# PANDASchematic.net
KiCad netlist of a schematic drawn in EAGLE
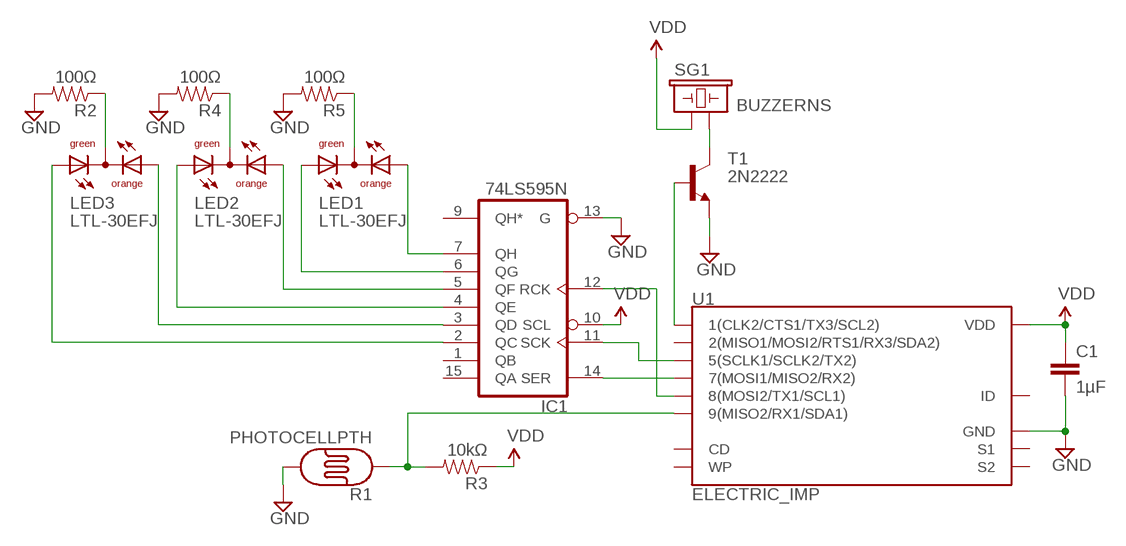
[diagram p0: schematic, sheet 1]

(export (version "E")
  (design (tool "Eeschema 10.0.6"))
  (components
    (comp (ref "C1")
      (value "1µF")
      (footprint "eagle-import:CAP-PTH-SMALL")
      (libsource (lib "eagle-import") (part "CAPPTH"))
    )
    (comp (ref "IC1")
      (value "74LS595N")
      (footprint "eagle-import:DIL16")
      (libsource (lib "eagle-import") (part "74595NLS"))
    )
    (comp (ref "LED1")
      (value "LTL-30EFJ")
      (footprint "eagle-import:TLUV5300")
      (libsource (lib "eagle-import") (part "TLUV5300"))
    )
    (comp (ref "LED2")
      (value "LTL-30EFJ")
      (footprint "eagle-import:TLUV5300")
      (libsource (lib "eagle-import") (part "TLUV5300"))
    )
    (comp (ref "LED3")
      (value "LTL-30EFJ")
      (footprint "eagle-import:TLUV5300")
      (libsource (lib "eagle-import") (part "TLUV5300"))
    )
    (comp (ref "R1")
      (value "PHOTOCELLPTH")
      (footprint "eagle-import:PHOTOCELL")
      (libsource (lib "eagle-import") (part "PHOTOCELLPTH"))
    )
    (comp (ref "R2")
      (value "100Ω")
      (footprint "eagle-import:AXIAL-0.3")
      (libsource (lib "eagle-import") (part "RESISTORAXIAL-0.3"))
    )
    (comp (ref "R3")
      (value "10kΩ")
      (footprint "eagle-import:AXIAL-0.3")
      (libsource (lib "eagle-import") (part "RESISTORAXIAL-0.3"))
    )
    (comp (ref "R4")
      (value "100Ω")
      (footprint "eagle-import:AXIAL-0.3")
      (libsource (lib "eagle-import") (part "RESISTORAXIAL-0.3"))
    )
    (comp (ref "R5")
      (value "100Ω")
      (footprint "eagle-import:AXIAL-0.3")
      (libsource (lib "eagle-import") (part "RESISTORAXIAL-0.3"))
    )
    (comp (ref "SG1")
      (value "BUZZERNS")
      (footprint "eagle-import:BUZZER-12MM-NS")
      (libsource (lib "eagle-import") (part "BUZZERNS"))
    )
    (comp (ref "T1")
      (value "2N2222")
      (footprint "eagle-import:TO92-EBC-OVAL")
      (libsource (lib "eagle-import") (part "2N2222"))
    )
    (comp (ref "U1")
      (value "ELECTRIC_IMP")
      (footprint "eagle-import:SD_1_1")
      (libsource (lib "eagle-import") (part "ELECTRIC_IMP"))
    )
  )
  (nets
    (net (code "1") (name "GND") (class "Default")
      (node (ref "C1") (pin "2") (pinfunction "2_2") (pintype "passive"))
      (node (ref "IC1") (pin "13") (pinfunction "G_13") (pintype "input"))
      (node (ref "R1") (pin "2") (pinfunction "P$2_2") (pintype "bidirectional"))
      (node (ref "R2") (pin "P$2") (pinfunction "2_P$2") (pintype "passive"))
      (node (ref "R4") (pin "P$2") (pinfunction "2_P$2") (pintype "passive"))
      (node (ref "R5") (pin "P$2") (pinfunction "2_P$2") (pintype "passive"))
      (node (ref "T1") (pin "E") (pinfunction "E_E") (pintype "passive"))
      (node (ref "U1") (pin "3") (pinfunction "GND_3") (pintype "bidirectional"))
    )
    (net (code "2") (name "Net-(IC1A-QC)") (class "Default")
      (node (ref "IC1") (pin "2") (pinfunction "QC_2") (pintype "tri_state"))
      (node (ref "LED3") (pin "AG") (pinfunction "AG_AG") (pintype "passive"))
    )
    (net (code "3") (name "Net-(IC1A-QD)") (class "Default")
      (node (ref "IC1") (pin "3") (pinfunction "QD_3") (pintype "tri_state"))
      (node (ref "LED3") (pin "AO") (pinfunction "AO_AO") (pintype "passive"))
    )
    (net (code "4") (name "Net-(IC1A-QE)") (class "Default")
      (node (ref "IC1") (pin "4") (pinfunction "QE_4") (pintype "tri_state"))
      (node (ref "LED2") (pin "AG") (pinfunction "AG_AG") (pintype "passive"))
    )
    (net (code "5") (name "Net-(IC1A-QF)") (class "Default")
      (node (ref "IC1") (pin "5") (pinfunction "QF_5") (pintype "tri_state"))
      (node (ref "LED2") (pin "AO") (pinfunction "AO_AO") (pintype "passive"))
    )
    (net (code "6") (name "Net-(IC1A-QG)") (class "Default")
      (node (ref "IC1") (pin "6") (pinfunction "QG_6") (pintype "tri_state"))
      (node (ref "LED1") (pin "AG") (pinfunction "AG_AG") (pintype "passive"))
    )
    (net (code "7") (name "Net-(IC1A-QH)") (class "Default")
      (node (ref "IC1") (pin "7") (pinfunction "QH_7") (pintype "tri_state"))
      (node (ref "LED1") (pin "AO") (pinfunction "AO_AO") (pintype "passive"))
    )
    (net (code "8") (name "Net-(IC1A-RCK)") (class "Default")
      (node (ref "IC1") (pin "12") (pinfunction "RCK_12") (pintype "input"))
      (node (ref "U1") (pin "8") (pinfunction "8(MOSI2/TX1/SCL1)_8") (pintype "bidirectional"))
    )
    (net (code "9") (name "Net-(IC1A-SCK)") (class "Default")
      (node (ref "IC1") (pin "11") (pinfunction "SCK_11") (pintype "input"))
      (node (ref "U1") (pin "5") (pinfunction "5(SCLK1/SCLK2/TX2)_5") (pintype "bidirectional"))
    )
    (net (code "10") (name "Net-(IC1A-SER)") (class "Default")
      (node (ref "IC1") (pin "14") (pinfunction "SER_14") (pintype "input"))
      (node (ref "U1") (pin "7") (pinfunction "7(MOSI1/MISO2/RX2)_7") (pintype "bidirectional"))
    )
    (net (code "11") (name "Net-(R1-P$1)") (class "Default")
      (node (ref "R1") (pin "1") (pinfunction "P$1_1") (pintype "bidirectional"))
      (node (ref "R3") (pin "P$2") (pinfunction "2_P$2") (pintype "passive"))
      (node (ref "U1") (pin "9") (pinfunction "9(MISO2/RX1/SDA1)_9") (pintype "bidirectional"))
    )
    (net (code "12") (name "Net-(R2-1)") (class "Default")
      (node (ref "LED3") (pin "CC") (pinfunction "CC_CC") (pintype "passive"))
      (node (ref "R2") (pin "P$1") (pinfunction "1_P$1") (pintype "passive"))
    )
    (net (code "13") (name "Net-(R4-1)") (class "Default")
      (node (ref "LED2") (pin "CC") (pinfunction "CC_CC") (pintype "passive"))
      (node (ref "R4") (pin "P$1") (pinfunction "1_P$1") (pintype "passive"))
    )
    (net (code "14") (name "Net-(R5-1)") (class "Default")
      (node (ref "LED1") (pin "CC") (pinfunction "CC_CC") (pintype "passive"))
      (node (ref "R5") (pin "P$1") (pinfunction "1_P$1") (pintype "passive"))
    )
    (net (code "15") (name "Net-(SG1-2)") (class "Default")
      (node (ref "SG1") (pin "-") (pinfunction "2_-") (pintype "passive"))
      (node (ref "T1") (pin "C") (pinfunction "C_C") (pintype "passive"))
    )
    (net (code "16") (name "Net-(U1-1(CLK2{slash}CTS1{slash}TX3{slash}SCL2))") (class "Default")
      (node (ref "T1") (pin "B") (pinfunction "B_B") (pintype "passive"))
      (node (ref "U1") (pin "1") (pinfunction "1(CLK2/CTS1/TX3/SCL2)_1") (pintype "bidirectional"))
    )
    (net (code "17") (name "VDD") (class "Default")
      (node (ref "C1") (pin "1") (pinfunction "1_1") (pintype "passive"))
      (node (ref "IC1") (pin "10") (pinfunction "SCL_10") (pintype "input"))
      (node (ref "R3") (pin "P$1") (pinfunction "1_P$1") (pintype "passive"))
      (node (ref "SG1") (pin "+") (pinfunction "1_+") (pintype "passive"))
      (node (ref "U1") (pin "4") (pinfunction "VDD_4") (pintype "bidirectional"))
    )
    (net (code "18") (name "unconnected-(IC1A-QA-Pad15)") (class "Default")
      (node (ref "IC1") (pin "15") (pinfunction "QA_15") (pintype "tri_state"))
    )
    (net (code "19") (name "unconnected-(IC1A-QB-Pad1)") (class "Default")
      (node (ref "IC1") (pin "1") (pinfunction "QB_1") (pintype "tri_state"))
    )
    (net (code "20") (name "unconnected-(IC1A-QH*-Pad9)") (class "Default")
      (node (ref "IC1") (pin "9") (pinfunction "QH*_9") (pintype "tri_state"))
    )
    (net (code "21") (name "unconnected-(U1-2(MISO1{slash}MOSI2{slash}RTS1{slash}RX3{slash}SDA2)-Pad2)") (class "Default")
      (node (ref "U1") (pin "2") (pinfunction "2(MISO1/MOSI2/RTS1/RX3/SDA2)_2") (pintype "bidirectional"))
    )
    (net (code "22") (name "unconnected-(U1-ID-Pad6)") (class "Default")
      (node (ref "U1") (pin "6") (pinfunction "ID_6") (pintype "bidirectional"))
    )
    (net (code "23") (name "unconnected-(U1-PadCD)") (class "Default")
      (node (ref "U1") (pin "CD") (pinfunction "CD_CD") (pintype "bidirectional"))
    )
    (net (code "24") (name "unconnected-(U1-PadWP)") (class "Default")
      (node (ref "U1") (pin "WP") (pinfunction "WP_WP") (pintype "bidirectional"))
    )
    (net (code "25") (name "unconnected-(U1-S1-PadSH@1)") (class "Default")
      (node (ref "U1") (pin "SH@1") (pinfunction "S1_SH@1") (pintype "bidirectional"))
    )
    (net (code "26") (name "unconnected-(U1-S2-PadSH@2)") (class "Default")
      (node (ref "U1") (pin "SH@2") (pinfunction "S2_SH@2") (pintype "bidirectional"))
    )
  )
)
